# lm5175_smps_v0001.net
KiCad netlist of a schematic drawn in EAGLE
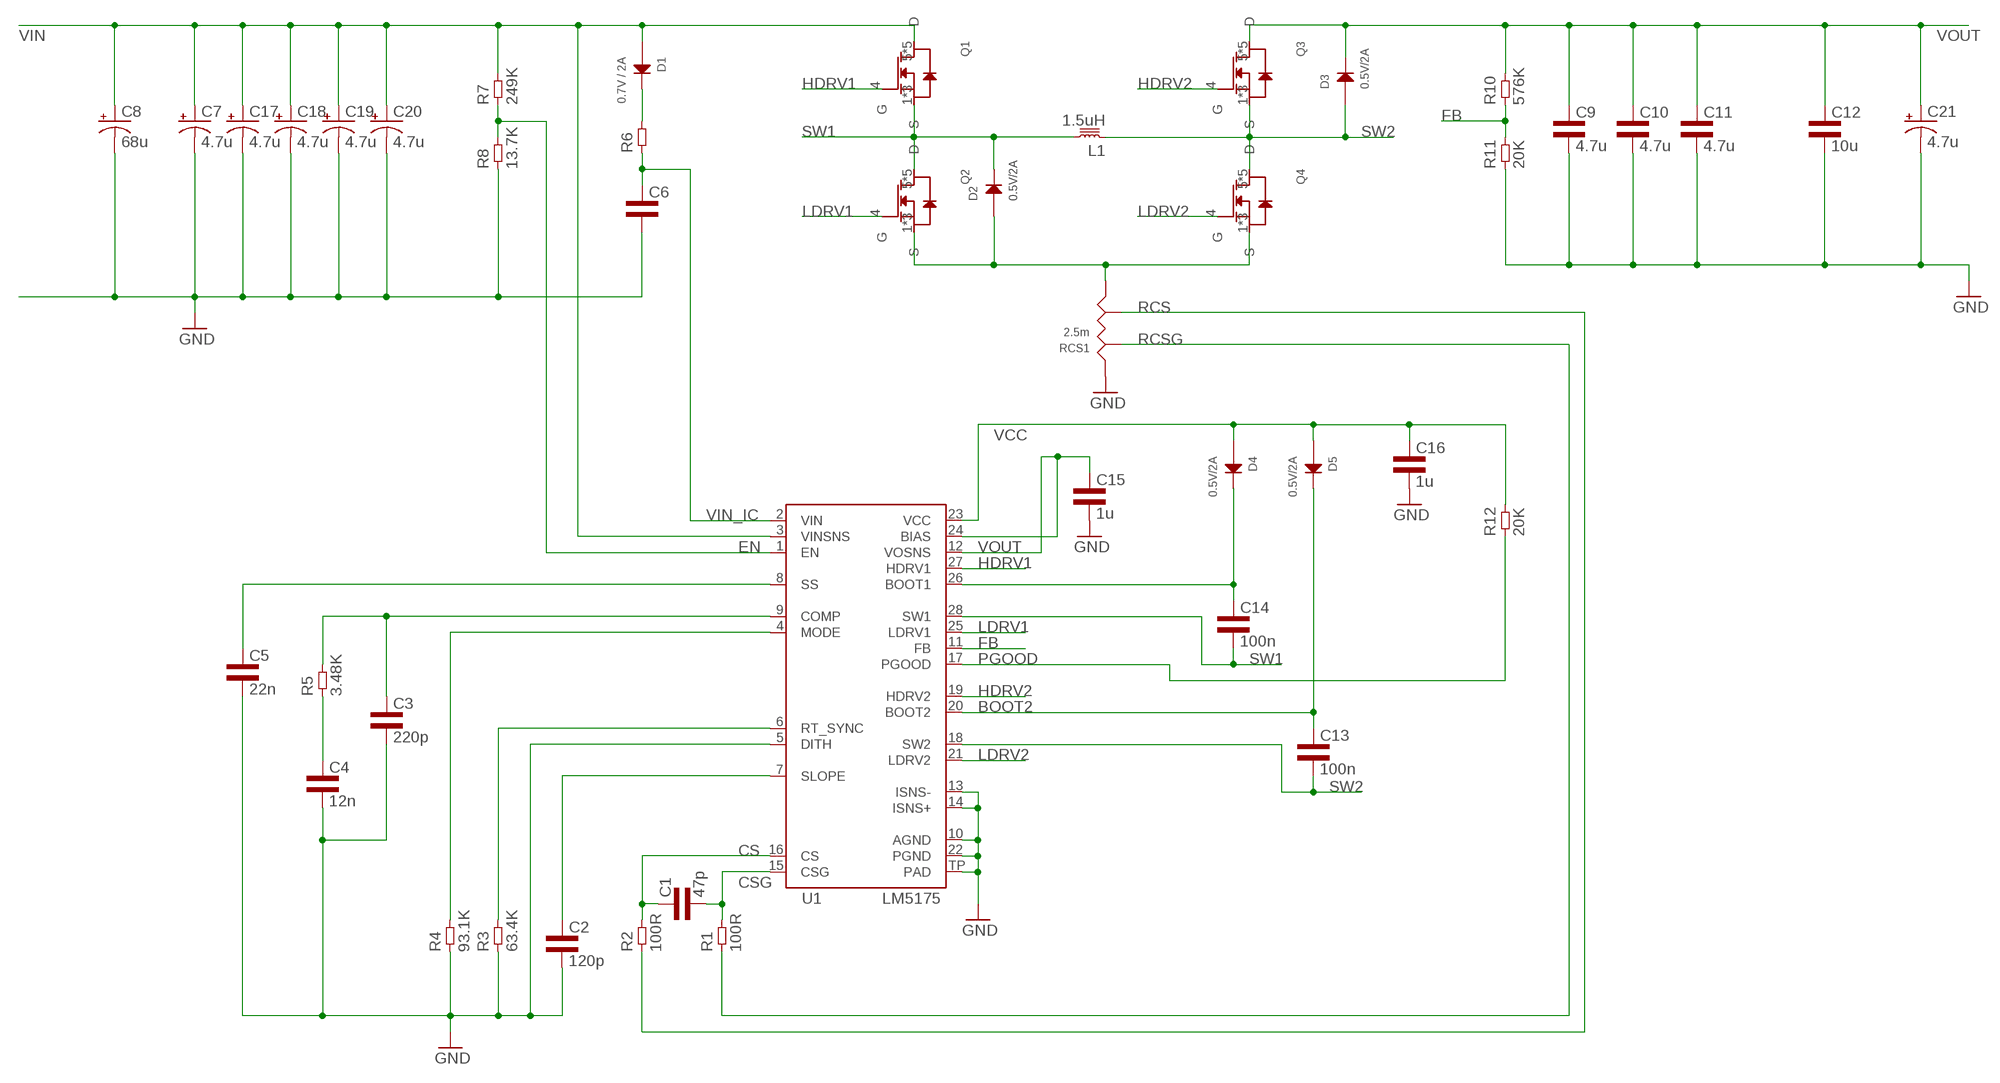
[diagram p0: schematic, sheet 1]

(export (version "E")
  (design (tool "Eeschema 10.0.6"))
  (components
    (comp (ref "C1")
      (value "47p")
      (footprint "eagle-import:0402L3")
      (libsource (lib "eagle-import") (part "CAP0402L3"))
    )
    (comp (ref "C2")
      (value "120p")
      (footprint "eagle-import:0603L3")
      (libsource (lib "eagle-import") (part "CAP0603L3"))
    )
    (comp (ref "C3")
      (value "220p")
      (footprint "eagle-import:0603L3")
      (libsource (lib "eagle-import") (part "CAP0603L3"))
    )
    (comp (ref "C4")
      (value "12n")
      (footprint "eagle-import:0603L3")
      (libsource (lib "eagle-import") (part "CAP0603L3"))
    )
    (comp (ref "C5")
      (value "22n")
      (footprint "eagle-import:0603L3")
      (libsource (lib "eagle-import") (part "CAP0603L3"))
    )
    (comp (ref "C6")
      (value "CAP0603L3")
      (footprint "eagle-import:0603L3")
      (libsource (lib "eagle-import") (part "CAP0603L3"))
    )
    (comp (ref "C7")
      (value "4.7u")
      (footprint "eagle-import:CT7343")
      (libsource (lib "eagle-import") (part "CPOL-USCT7343"))
    )
    (comp (ref "C8")
      (value "68u")
      (footprint "eagle-import:153CLV-0810")
      (libsource (lib "eagle-import") (part "CPOL-US153CLV-0810"))
    )
    (comp (ref "C9")
      (value "4.7u")
      (footprint "eagle-import:1206L3")
      (libsource (lib "eagle-import") (part "CAP1206L3"))
    )
    (comp (ref "C10")
      (value "4.7u")
      (footprint "eagle-import:1206L3")
      (libsource (lib "eagle-import") (part "CAP1206L3"))
    )
    (comp (ref "C11")
      (value "4.7u")
      (footprint "eagle-import:1206L3")
      (libsource (lib "eagle-import") (part "CAP1206L3"))
    )
    (comp (ref "C12")
      (value "10u")
      (footprint "eagle-import:1206L3")
      (libsource (lib "eagle-import") (part "CAP1206L3"))
    )
    (comp (ref "C13")
      (value "100n")
      (footprint "eagle-import:0603L3")
      (libsource (lib "eagle-import") (part "CAP0603L3"))
    )
    (comp (ref "C14")
      (value "100n")
      (footprint "eagle-import:0603L3")
      (libsource (lib "eagle-import") (part "CAP0603L3"))
    )
    (comp (ref "C15")
      (value "1u")
      (footprint "eagle-import:0603L3")
      (libsource (lib "eagle-import") (part "CAP0603L3"))
    )
    (comp (ref "C16")
      (value "1u")
      (footprint "eagle-import:0603L3")
      (libsource (lib "eagle-import") (part "CAP0603L3"))
    )
    (comp (ref "C17")
      (value "4.7u")
      (footprint "eagle-import:CT7343")
      (libsource (lib "eagle-import") (part "CPOL-USCT7343"))
    )
    (comp (ref "C18")
      (value "4.7u")
      (footprint "eagle-import:CT7343")
      (libsource (lib "eagle-import") (part "CPOL-USCT7343"))
    )
    (comp (ref "C19")
      (value "4.7u")
      (footprint "eagle-import:CT7343")
      (libsource (lib "eagle-import") (part "CPOL-USCT7343"))
    )
    (comp (ref "C20")
      (value "4.7u")
      (footprint "eagle-import:CT7343")
      (libsource (lib "eagle-import") (part "CPOL-USCT7343"))
    )
    (comp (ref "C21")
      (value "4.7u")
      (footprint "eagle-import:SANYO-OSCON_SMD_E12")
      (libsource (lib "eagle-import") (part "CPOL-USSANYO_SMD_E12"))
    )
    (comp (ref "D1")
      (value "0.7V / 2A")
      (footprint "eagle-import:SMA-2")
      (libsource (lib "eagle-import") (part "DIODESMA"))
    )
    (comp (ref "D2")
      (value "0.5V/2A")
      (footprint "eagle-import:SMA-2")
      (libsource (lib "eagle-import") (part "DIODESMA"))
    )
    (comp (ref "D3")
      (value "0.5V/2A")
      (footprint "eagle-import:SMA-2")
      (libsource (lib "eagle-import") (part "DIODESMA"))
    )
    (comp (ref "D4")
      (value "0.5V/2A")
      (footprint "eagle-import:SMA-2")
      (libsource (lib "eagle-import") (part "DIODESMA"))
    )
    (comp (ref "D5")
      (value "0.5V/2A")
      (footprint "eagle-import:SMA-2")
      (libsource (lib "eagle-import") (part "DIODESMA"))
    )
    (comp (ref "L1")
      (value "1.5uH")
      (footprint "eagle-import:5.7X5.2")
      (libsource (lib "eagle-import") (part "INDUCTOR5752"))
    )
    (comp (ref "Q1")
      (value "CSD18540Q5B")
      (footprint "eagle-import:Q5B")
      (libsource (lib "eagle-import") (part "CSD18540Q5B"))
    )
    (comp (ref "Q2")
      (value "CSD18540Q5B")
      (footprint "eagle-import:Q5B")
      (libsource (lib "eagle-import") (part "CSD18540Q5B"))
    )
    (comp (ref "Q3")
      (value "CSD18540Q5B")
      (footprint "eagle-import:Q5B")
      (libsource (lib "eagle-import") (part "CSD18540Q5B"))
    )
    (comp (ref "Q4")
      (value "CSD18540Q5B")
      (footprint "eagle-import:Q5B")
      (libsource (lib "eagle-import") (part "CSD18540Q5B"))
    )
    (comp (ref "R1")
      (value "100R")
      (footprint "eagle-import:0603L3")
      (libsource (lib "eagle-import") (part "RES0603L3"))
    )
    (comp (ref "R2")
      (value "100R")
      (footprint "eagle-import:0603L3")
      (libsource (lib "eagle-import") (part "RES0603L3"))
    )
    (comp (ref "R3")
      (value "63.4K")
      (footprint "eagle-import:0603L3")
      (libsource (lib "eagle-import") (part "RES0603L3"))
    )
    (comp (ref "R4")
      (value "93.1K")
      (footprint "eagle-import:0603L3")
      (libsource (lib "eagle-import") (part "RES0603L3"))
    )
    (comp (ref "R5")
      (value "3.48K")
      (footprint "eagle-import:0603L3")
      (libsource (lib "eagle-import") (part "RES0603L3"))
    )
    (comp (ref "R6")
      (value "RES0603L3")
      (footprint "eagle-import:0603L3")
      (libsource (lib "eagle-import") (part "RES0603L3"))
    )
    (comp (ref "R7")
      (value "249K")
      (footprint "eagle-import:0603L3")
      (libsource (lib "eagle-import") (part "RES0603L3"))
    )
    (comp (ref "R8")
      (value "13.7K")
      (footprint "eagle-import:0603L3")
      (libsource (lib "eagle-import") (part "RES0603L3"))
    )
    (comp (ref "R10")
      (value "576K")
      (footprint "eagle-import:0603L3")
      (libsource (lib "eagle-import") (part "RES0603L3"))
    )
    (comp (ref "R11")
      (value "20K")
      (footprint "eagle-import:0603L3")
      (libsource (lib "eagle-import") (part "RES0603L3"))
    )
    (comp (ref "R12")
      (value "20K")
      (footprint "eagle-import:0603L3")
      (libsource (lib "eagle-import") (part "RES0603L3"))
    )
    (comp (ref "RCS1")
      (value "2.5m")
      (footprint "eagle-import:R2512")
      (libsource (lib "eagle-import") (part "CSRES"))
    )
    (comp (ref "U1")
      (value "LM5175")
      (footprint "eagle-import:R-PDSO-G28")
      (libsource (lib "eagle-import") (part "LM5175"))
    )
  )
  (nets
    (net (code "1") (name "/BOOT2") (class "Default")
      (node (ref "C13") (pin "P$1") (pinfunction "1_P$1") (pintype "bidirectional"))
      (node (ref "D5") (pin "2") (pinfunction "CATHODE_2") (pintype "bidirectional"))
      (node (ref "U1") (pin "20") (pinfunction "BOOT2_20") (pintype "bidirectional"))
    )
    (net (code "2") (name "/CS") (class "Default")
      (node (ref "C1") (pin "P$1") (pinfunction "1_P$1") (pintype "bidirectional"))
      (node (ref "R2") (pin "P$2") (pinfunction "2_P$2") (pintype "bidirectional"))
      (node (ref "U1") (pin "16") (pinfunction "CS_16") (pintype "bidirectional"))
    )
    (net (code "3") (name "/CSG") (class "Default")
      (node (ref "C1") (pin "P$2") (pinfunction "2_P$2") (pintype "bidirectional"))
      (node (ref "R1") (pin "P$2") (pinfunction "2_P$2") (pintype "bidirectional"))
      (node (ref "U1") (pin "15") (pinfunction "CSG_15") (pintype "bidirectional"))
    )
    (net (code "4") (name "/EN") (class "Default")
      (node (ref "R7") (pin "P$1") (pinfunction "1_P$1") (pintype "bidirectional"))
      (node (ref "R8") (pin "P$2") (pinfunction "2_P$2") (pintype "bidirectional"))
      (node (ref "U1") (pin "1") (pinfunction "EN_1") (pintype "bidirectional"))
    )
    (net (code "5") (name "/FB") (class "Default")
      (node (ref "R10") (pin "P$1") (pinfunction "1_P$1") (pintype "bidirectional"))
      (node (ref "R11") (pin "P$2") (pinfunction "2_P$2") (pintype "bidirectional"))
      (node (ref "U1") (pin "11") (pinfunction "FB_11") (pintype "bidirectional"))
    )
    (net (code "6") (name "/HDRV1") (class "Default")
      (node (ref "Q1") (pin "4") (pinfunction "G_4") (pintype "bidirectional"))
      (node (ref "U1") (pin "27") (pinfunction "HDRV1_27") (pintype "bidirectional"))
    )
    (net (code "7") (name "/HDRV2") (class "Default")
      (node (ref "Q3") (pin "4") (pinfunction "G_4") (pintype "bidirectional"))
      (node (ref "U1") (pin "19") (pinfunction "HDRV2_19") (pintype "bidirectional"))
    )
    (net (code "8") (name "/LDRV1") (class "Default")
      (node (ref "Q2") (pin "4") (pinfunction "G_4") (pintype "bidirectional"))
      (node (ref "U1") (pin "25") (pinfunction "LDRV1_25") (pintype "bidirectional"))
    )
    (net (code "9") (name "/LDRV2") (class "Default")
      (node (ref "Q4") (pin "4") (pinfunction "G_4") (pintype "bidirectional"))
      (node (ref "U1") (pin "21") (pinfunction "LDRV2_21") (pintype "bidirectional"))
    )
    (net (code "10") (name "/PGOOD") (class "Default")
      (node (ref "R12") (pin "P$1") (pinfunction "1_P$1") (pintype "bidirectional"))
      (node (ref "U1") (pin "17") (pinfunction "PGOOD_17") (pintype "bidirectional"))
    )
    (net (code "11") (name "/RCS") (class "Default")
      (node (ref "R2") (pin "P$1") (pinfunction "1_P$1") (pintype "bidirectional"))
      (node (ref "RCS1") (pin "CS_2") (pinfunction "CS_2_CS_2") (pintype "bidirectional"))
    )
    (net (code "12") (name "/RCSG") (class "Default")
      (node (ref "R1") (pin "P$1") (pinfunction "1_P$1") (pintype "bidirectional"))
      (node (ref "RCS1") (pin "CS_1") (pinfunction "CS_1_CS_1") (pintype "bidirectional"))
    )
    (net (code "13") (name "/SW1") (class "Default")
      (node (ref "C14") (pin "P$2") (pinfunction "2_P$2") (pintype "bidirectional"))
      (node (ref "D2") (pin "2") (pinfunction "CATHODE_2") (pintype "bidirectional"))
      (node (ref "L1") (pin "2") (pinfunction "2_2") (pintype "bidirectional"))
      (node (ref "Q1") (pin "1") (pinfunction "S_1") (pintype "bidirectional"))
      (node (ref "Q1") (pin "2") (pinfunction "S_2") (pintype "bidirectional"))
      (node (ref "Q1") (pin "3") (pinfunction "S_3") (pintype "bidirectional"))
      (node (ref "Q2") (pin "5") (pinfunction "D_5") (pintype "bidirectional"))
      (node (ref "Q2") (pin "6") (pinfunction "D_6") (pintype "bidirectional"))
      (node (ref "Q2") (pin "7") (pinfunction "D_7") (pintype "bidirectional"))
      (node (ref "Q2") (pin "8") (pinfunction "D_8") (pintype "bidirectional"))
      (node (ref "Q2") (pin "9") (pinfunction "D_9") (pintype "bidirectional"))
      (node (ref "U1") (pin "28") (pinfunction "SW1_28") (pintype "bidirectional"))
    )
    (net (code "14") (name "/SW2") (class "Default")
      (node (ref "C13") (pin "P$2") (pinfunction "2_P$2") (pintype "bidirectional"))
      (node (ref "D3") (pin "1") (pinfunction "ANODE_1") (pintype "bidirectional"))
      (node (ref "L1") (pin "1") (pinfunction "1_1") (pintype "bidirectional"))
      (node (ref "Q3") (pin "1") (pinfunction "S_1") (pintype "bidirectional"))
      (node (ref "Q3") (pin "2") (pinfunction "S_2") (pintype "bidirectional"))
      (node (ref "Q3") (pin "3") (pinfunction "S_3") (pintype "bidirectional"))
      (node (ref "Q4") (pin "5") (pinfunction "D_5") (pintype "bidirectional"))
      (node (ref "Q4") (pin "6") (pinfunction "D_6") (pintype "bidirectional"))
      (node (ref "Q4") (pin "7") (pinfunction "D_7") (pintype "bidirectional"))
      (node (ref "Q4") (pin "8") (pinfunction "D_8") (pintype "bidirectional"))
      (node (ref "Q4") (pin "9") (pinfunction "D_9") (pintype "bidirectional"))
      (node (ref "U1") (pin "18") (pinfunction "SW2_18") (pintype "bidirectional"))
    )
    (net (code "15") (name "/VCC") (class "Default")
      (node (ref "C16") (pin "P$1") (pinfunction "1_P$1") (pintype "bidirectional"))
      (node (ref "D4") (pin "1") (pinfunction "ANODE_1") (pintype "bidirectional"))
      (node (ref "D5") (pin "1") (pinfunction "ANODE_1") (pintype "bidirectional"))
      (node (ref "R12") (pin "P$2") (pinfunction "2_P$2") (pintype "bidirectional"))
      (node (ref "U1") (pin "23") (pinfunction "VCC_23") (pintype "bidirectional"))
    )
    (net (code "16") (name "/VIN") (class "Default")
      (node (ref "C17") (pin "+") (pinfunction "+_+") (pintype "passive"))
      (node (ref "C18") (pin "+") (pinfunction "+_+") (pintype "passive"))
      (node (ref "C19") (pin "+") (pinfunction "+_+") (pintype "passive"))
      (node (ref "C20") (pin "+") (pinfunction "+_+") (pintype "passive"))
      (node (ref "C7") (pin "+") (pinfunction "+_+") (pintype "passive"))
      (node (ref "C8") (pin "+") (pinfunction "+_+") (pintype "passive"))
      (node (ref "D1") (pin "1") (pinfunction "ANODE_1") (pintype "bidirectional"))
      (node (ref "Q1") (pin "5") (pinfunction "D_5") (pintype "bidirectional"))
      (node (ref "Q1") (pin "6") (pinfunction "D_6") (pintype "bidirectional"))
      (node (ref "Q1") (pin "7") (pinfunction "D_7") (pintype "bidirectional"))
      (node (ref "Q1") (pin "8") (pinfunction "D_8") (pintype "bidirectional"))
      (node (ref "Q1") (pin "9") (pinfunction "D_9") (pintype "bidirectional"))
      (node (ref "R7") (pin "P$2") (pinfunction "2_P$2") (pintype "bidirectional"))
      (node (ref "U1") (pin "3") (pinfunction "VINSNS_3") (pintype "bidirectional"))
    )
    (net (code "17") (name "/VIN_IC") (class "Default")
      (node (ref "C6") (pin "P$1") (pinfunction "1_P$1") (pintype "bidirectional"))
      (node (ref "R6") (pin "P$1") (pinfunction "1_P$1") (pintype "bidirectional"))
      (node (ref "U1") (pin "2") (pinfunction "VIN_2") (pintype "bidirectional"))
    )
    (net (code "18") (name "/VOUT") (class "Default")
      (node (ref "C10") (pin "1") (pinfunction "1_1") (pintype "bidirectional"))
      (node (ref "C11") (pin "1") (pinfunction "1_1") (pintype "bidirectional"))
      (node (ref "C12") (pin "1") (pinfunction "1_1") (pintype "bidirectional"))
      (node (ref "C15") (pin "P$1") (pinfunction "1_P$1") (pintype "bidirectional"))
      (node (ref "C21") (pin "+") (pinfunction "+_+") (pintype "passive"))
      (node (ref "C9") (pin "1") (pinfunction "1_1") (pintype "bidirectional"))
      (node (ref "D3") (pin "2") (pinfunction "CATHODE_2") (pintype "bidirectional"))
      (node (ref "Q3") (pin "5") (pinfunction "D_5") (pintype "bidirectional"))
      (node (ref "Q3") (pin "6") (pinfunction "D_6") (pintype "bidirectional"))
      (node (ref "Q3") (pin "7") (pinfunction "D_7") (pintype "bidirectional"))
      (node (ref "Q3") (pin "8") (pinfunction "D_8") (pintype "bidirectional"))
      (node (ref "Q3") (pin "9") (pinfunction "D_9") (pintype "bidirectional"))
      (node (ref "R10") (pin "P$2") (pinfunction "2_P$2") (pintype "bidirectional"))
      (node (ref "U1") (pin "12") (pinfunction "VOSNS_12") (pintype "bidirectional"))
      (node (ref "U1") (pin "24") (pinfunction "BIAS_24") (pintype "bidirectional"))
    )
    (net (code "19") (name "GND") (class "Default")
      (node (ref "C10") (pin "2") (pinfunction "2_2") (pintype "bidirectional"))
      (node (ref "C11") (pin "2") (pinfunction "2_2") (pintype "bidirectional"))
      (node (ref "C12") (pin "2") (pinfunction "2_2") (pintype "bidirectional"))
      (node (ref "C15") (pin "P$2") (pinfunction "2_P$2") (pintype "bidirectional"))
      (node (ref "C16") (pin "P$2") (pinfunction "2_P$2") (pintype "bidirectional"))
      (node (ref "C17") (pin "-") (pinfunction "-_-") (pintype "passive"))
      (node (ref "C18") (pin "-") (pinfunction "-_-") (pintype "passive"))
      (node (ref "C19") (pin "-") (pinfunction "-_-") (pintype "passive"))
      (node (ref "C2") (pin "P$2") (pinfunction "2_P$2") (pintype "bidirectional"))
      (node (ref "C20") (pin "-") (pinfunction "-_-") (pintype "passive"))
      (node (ref "C21") (pin "-") (pinfunction "-_-") (pintype "passive"))
      (node (ref "C3") (pin "P$2") (pinfunction "2_P$2") (pintype "bidirectional"))
      (node (ref "C4") (pin "P$2") (pinfunction "2_P$2") (pintype "bidirectional"))
      (node (ref "C5") (pin "P$2") (pinfunction "2_P$2") (pintype "bidirectional"))
      (node (ref "C6") (pin "P$2") (pinfunction "2_P$2") (pintype "bidirectional"))
      (node (ref "C7") (pin "-") (pinfunction "-_-") (pintype "passive"))
      (node (ref "C8") (pin "-") (pinfunction "-_-") (pintype "passive"))
      (node (ref "C9") (pin "2") (pinfunction "2_2") (pintype "bidirectional"))
      (node (ref "R11") (pin "P$1") (pinfunction "1_P$1") (pintype "bidirectional"))
      (node (ref "R3") (pin "P$1") (pinfunction "1_P$1") (pintype "bidirectional"))
      (node (ref "R4") (pin "P$1") (pinfunction "1_P$1") (pintype "bidirectional"))
      (node (ref "R8") (pin "P$1") (pinfunction "1_P$1") (pintype "bidirectional"))
      (node (ref "RCS1") (pin "1_1") (pinfunction "1_1_1") (pintype "bidirectional"))
      (node (ref "RCS1") (pin "1_2") (pinfunction "1_1_2") (pintype "bidirectional"))
      (node (ref "U1") (pin "10") (pinfunction "AGND_10") (pintype "bidirectional"))
      (node (ref "U1") (pin "13") (pinfunction "ISNS-_13") (pintype "bidirectional"))
      (node (ref "U1") (pin "14") (pinfunction "ISNS+_14") (pintype "bidirectional"))
      (node (ref "U1") (pin "22") (pinfunction "PGND_22") (pintype "bidirectional"))
      (node (ref "U1") (pin "5") (pinfunction "DITH_5") (pintype "bidirectional"))
      (node (ref "U1") (pin "TP") (pinfunction "PAD_TP") (pintype "bidirectional"))
    )
    (net (code "20") (name "Net-(C2-1)") (class "Default")
      (node (ref "C2") (pin "P$1") (pinfunction "1_P$1") (pintype "bidirectional"))
      (node (ref "U1") (pin "7") (pinfunction "SLOPE_7") (pintype "bidirectional"))
    )
    (net (code "21") (name "Net-(C3-1)") (class "Default")
      (node (ref "C3") (pin "P$1") (pinfunction "1_P$1") (pintype "bidirectional"))
      (node (ref "R5") (pin "P$2") (pinfunction "2_P$2") (pintype "bidirectional"))
      (node (ref "U1") (pin "9") (pinfunction "COMP_9") (pintype "bidirectional"))
    )
    (net (code "22") (name "Net-(C4-1)") (class "Default")
      (node (ref "C4") (pin "P$1") (pinfunction "1_P$1") (pintype "bidirectional"))
      (node (ref "R5") (pin "P$1") (pinfunction "1_P$1") (pintype "bidirectional"))
    )
    (net (code "23") (name "Net-(C5-1)") (class "Default")
      (node (ref "C5") (pin "P$1") (pinfunction "1_P$1") (pintype "bidirectional"))
      (node (ref "U1") (pin "8") (pinfunction "SS_8") (pintype "bidirectional"))
    )
    (net (code "24") (name "Net-(C14-1)") (class "Default")
      (node (ref "C14") (pin "P$1") (pinfunction "1_P$1") (pintype "bidirectional"))
      (node (ref "D4") (pin "2") (pinfunction "CATHODE_2") (pintype "bidirectional"))
      (node (ref "U1") (pin "26") (pinfunction "BOOT1_26") (pintype "bidirectional"))
    )
    (net (code "25") (name "Net-(D1-CATHODE)") (class "Default")
      (node (ref "D1") (pin "2") (pinfunction "CATHODE_2") (pintype "bidirectional"))
      (node (ref "R6") (pin "P$2") (pinfunction "2_P$2") (pintype "bidirectional"))
    )
    (net (code "26") (name "Net-(D2-ANODE)") (class "Default")
      (node (ref "D2") (pin "1") (pinfunction "ANODE_1") (pintype "bidirectional"))
      (node (ref "Q2") (pin "1") (pinfunction "S_1") (pintype "bidirectional"))
      (node (ref "Q2") (pin "2") (pinfunction "S_2") (pintype "bidirectional"))
      (node (ref "Q2") (pin "3") (pinfunction "S_3") (pintype "bidirectional"))
      (node (ref "Q4") (pin "1") (pinfunction "S_1") (pintype "bidirectional"))
      (node (ref "Q4") (pin "2") (pinfunction "S_2") (pintype "bidirectional"))
      (node (ref "Q4") (pin "3") (pinfunction "S_3") (pintype "bidirectional"))
      (node (ref "RCS1") (pin "2_1") (pinfunction "2_2_1") (pintype "bidirectional"))
      (node (ref "RCS1") (pin "2_2") (pinfunction "2_2_2") (pintype "bidirectional"))
    )
    (net (code "27") (name "Net-(R3-2)") (class "Default")
      (node (ref "R3") (pin "P$2") (pinfunction "2_P$2") (pintype "bidirectional"))
      (node (ref "U1") (pin "6") (pinfunction "RT_SYNC_6") (pintype "bidirectional"))
    )
    (net (code "28") (name "Net-(R4-2)") (class "Default")
      (node (ref "R4") (pin "P$2") (pinfunction "2_P$2") (pintype "bidirectional"))
      (node (ref "U1") (pin "4") (pinfunction "MODE_4") (pintype "bidirectional"))
    )
  )
)
